# current_amplifier_02.net
KiCad netlist of a schematic drawn in Altium Designer
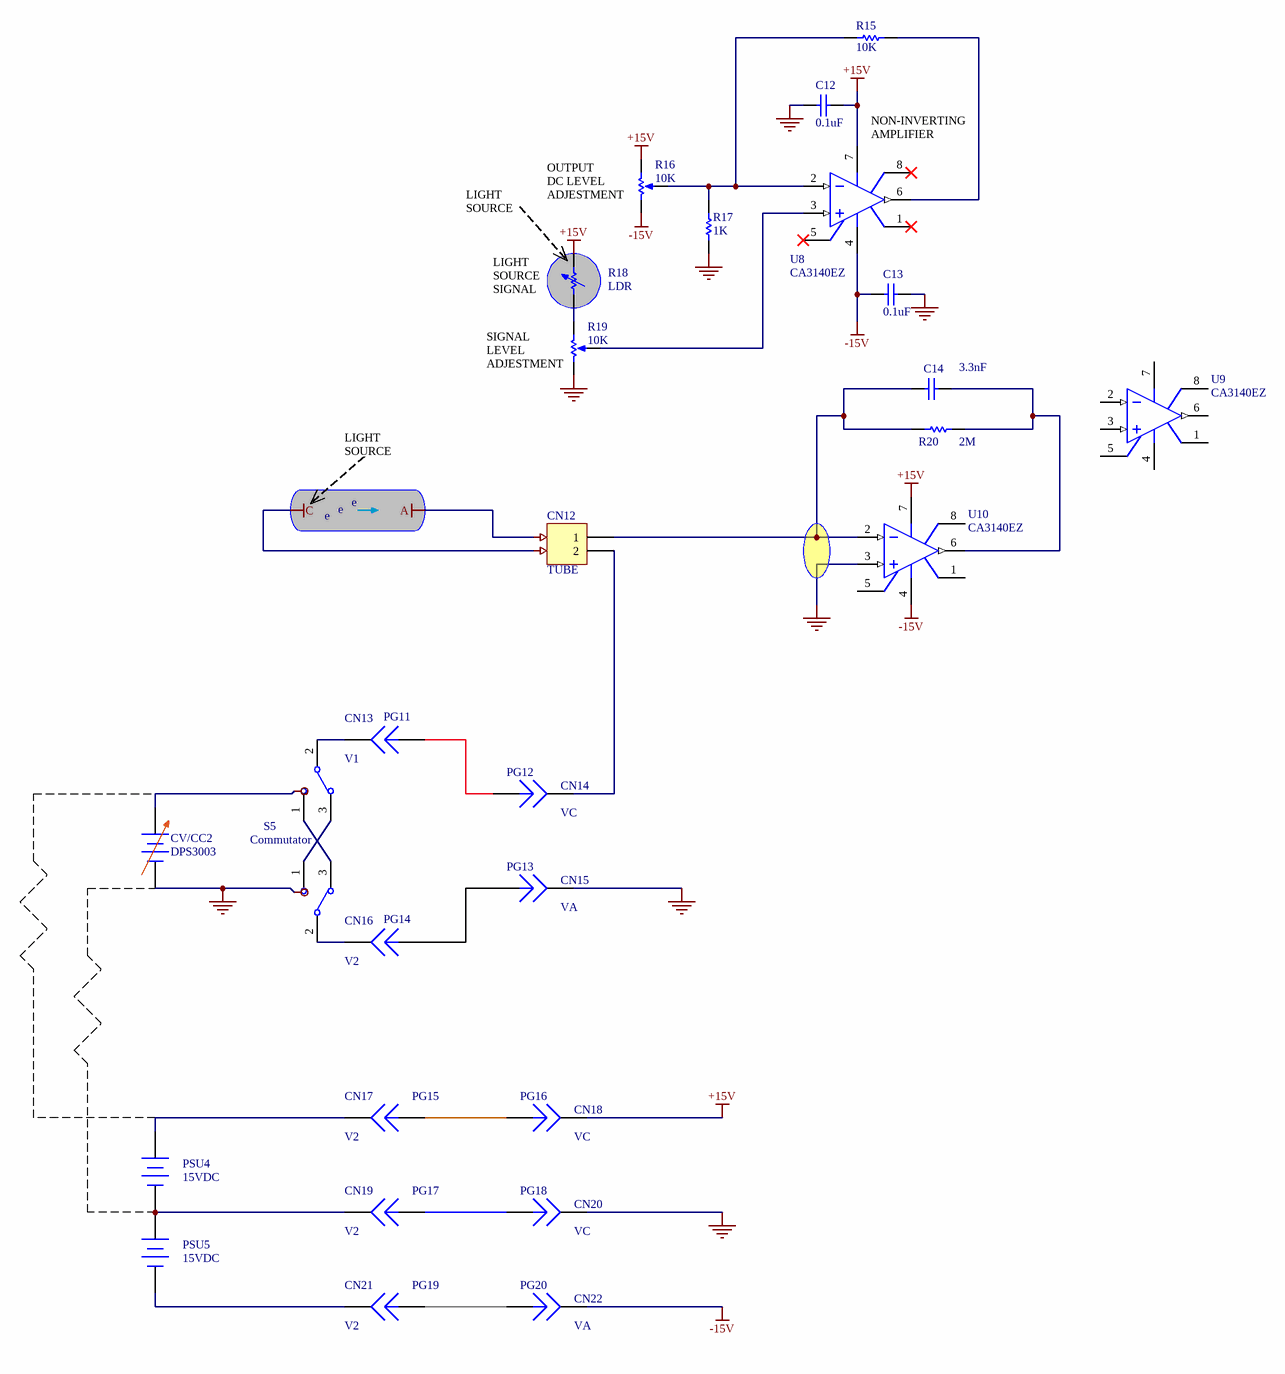
[diagram p0: current amplifier 02.SchDoc]

(export (version "E")
  (design (tool "Eeschema 10.0.6"))
  (components
    (comp (ref "C12")
      (value "0.1uF")
      (footprint "RAD-0.3")
      (description "Capacitor")
      (fields (field (name "PUBLISHER") "Altium Limited"))
      (libsource (lib "Miscellaneous Devices") (part "Cap"))
    )
    (comp (ref "C13")
      (value "0.1uF")
      (footprint "RAD-0.3")
      (description "Capacitor")
      (fields (field (name "PUBLISHER") "Altium Limited"))
      (libsource (lib "Miscellaneous Devices") (part "Cap"))
    )
    (comp (ref "C14")
      (value "3.3nF")
      (footprint "RAD-0.3")
      (description "Capacitor")
      (fields (field (name "PUBLISHER") "Altium Limited"))
      (libsource (lib "Miscellaneous Devices") (part "Cap"))
    )
    (comp (ref "CN12")
      (value "TUBE")
      (footprint "HDR1X2")
      (description "Header, 2-Pin")
      (fields (field (name "PUBLISHER") "Altium Limited"))
      (libsource (lib "Miscellaneous Connectors") (part "Header 2"))
    )
    (comp (ref "CN13")
      (value "V1")
      (footprint "PIN1")
      (description "Socket")
      (fields (field (name "PUBLISHER") "Altium Limited"))
      (libsource (lib "Miscellaneous Connectors") (part "Socket"))
    )
    (comp (ref "CN14")
      (value "VC")
      (footprint "PIN1")
      (description "Socket")
      (fields (field (name "PUBLISHER") "Altium Limited"))
      (libsource (lib "Miscellaneous Connectors") (part "Socket"))
    )
    (comp (ref "CN15")
      (value "VA")
      (footprint "PIN1")
      (description "Socket")
      (fields (field (name "PUBLISHER") "Altium Limited"))
      (libsource (lib "Miscellaneous Connectors") (part "Socket"))
    )
    (comp (ref "CN16")
      (value "V2")
      (footprint "PIN1")
      (description "Socket")
      (fields (field (name "PUBLISHER") "Altium Limited"))
      (libsource (lib "Miscellaneous Connectors") (part "Socket"))
    )
    (comp (ref "CN17")
      (value "V2")
      (footprint "PIN1")
      (description "Socket")
      (fields (field (name "PUBLISHER") "Altium Limited"))
      (libsource (lib "Miscellaneous Connectors") (part "Socket"))
    )
    (comp (ref "CN18")
      (value "VC")
      (footprint "PIN1")
      (description "Socket")
      (fields (field (name "PUBLISHER") "Altium Limited"))
      (libsource (lib "Miscellaneous Connectors") (part "Socket"))
    )
    (comp (ref "CN19")
      (value "V2")
      (footprint "PIN1")
      (description "Socket")
      (fields (field (name "PUBLISHER") "Altium Limited"))
      (libsource (lib "Miscellaneous Connectors") (part "Socket"))
    )
    (comp (ref "CN20")
      (value "VC")
      (footprint "PIN1")
      (description "Socket")
      (fields (field (name "PUBLISHER") "Altium Limited"))
      (libsource (lib "Miscellaneous Connectors") (part "Socket"))
    )
    (comp (ref "CN21")
      (value "V2")
      (footprint "PIN1")
      (description "Socket")
      (fields (field (name "PUBLISHER") "Altium Limited"))
      (libsource (lib "Miscellaneous Connectors") (part "Socket"))
    )
    (comp (ref "CN22")
      (value "VA")
      (footprint "PIN1")
      (description "Socket")
      (fields (field (name "PUBLISHER") "Altium Limited"))
      (libsource (lib "Miscellaneous Connectors") (part "Socket"))
    )
    (comp (ref "CV/CC2")
      (value "DPS3003")
      (footprint "BAT-2")
      (description "Multicell Battery")
      (fields (field (name "PUBLISHER") "Altium Limited"))
      (libsource (lib "Miscellaneous Devices") (part "Battery"))
    )
    (comp (ref "PG11")
      (value "Plug")
      (footprint "PIN1")
      (fields (field (name "PUBLISHER") "Altium Limited"))
      (libsource (lib "Miscellaneous Connectors") (part "Plug"))
    )
    (comp (ref "PG12")
      (value "Plug")
      (footprint "PIN1")
      (fields (field (name "PUBLISHER") "Altium Limited"))
      (libsource (lib "Miscellaneous Connectors") (part "Plug"))
    )
    (comp (ref "PG13")
      (value "Plug")
      (footprint "PIN1")
      (fields (field (name "PUBLISHER") "Altium Limited"))
      (libsource (lib "Miscellaneous Connectors") (part "Plug"))
    )
    (comp (ref "PG14")
      (value "Plug")
      (footprint "PIN1")
      (fields (field (name "PUBLISHER") "Altium Limited"))
      (libsource (lib "Miscellaneous Connectors") (part "Plug"))
    )
    (comp (ref "PG15")
      (value "Plug")
      (footprint "PIN1")
      (fields (field (name "PUBLISHER") "Altium Limited"))
      (libsource (lib "Miscellaneous Connectors") (part "Plug"))
    )
    (comp (ref "PG16")
      (value "Plug")
      (footprint "PIN1")
      (fields (field (name "PUBLISHER") "Altium Limited"))
      (libsource (lib "Miscellaneous Connectors") (part "Plug"))
    )
    (comp (ref "PG17")
      (value "Plug")
      (footprint "PIN1")
      (fields (field (name "PUBLISHER") "Altium Limited"))
      (libsource (lib "Miscellaneous Connectors") (part "Plug"))
    )
    (comp (ref "PG18")
      (value "Plug")
      (footprint "PIN1")
      (fields (field (name "PUBLISHER") "Altium Limited"))
      (libsource (lib "Miscellaneous Connectors") (part "Plug"))
    )
    (comp (ref "PG19")
      (value "Plug")
      (footprint "PIN1")
      (fields (field (name "PUBLISHER") "Altium Limited"))
      (libsource (lib "Miscellaneous Connectors") (part "Plug"))
    )
    (comp (ref "PG20")
      (value "Plug")
      (footprint "PIN1")
      (fields (field (name "PUBLISHER") "Altium Limited"))
      (libsource (lib "Miscellaneous Connectors") (part "Plug"))
    )
    (comp (ref "PSU4")
      (value "15VDC")
      (footprint "BAT-2")
      (description "Multicell Battery")
      (fields (field (name "PUBLISHER") "Altium Limited"))
      (libsource (lib "Miscellaneous Devices") (part "Battery"))
    )
    (comp (ref "PSU5")
      (value "15VDC")
      (footprint "BAT-2")
      (description "Multicell Battery")
      (fields (field (name "PUBLISHER") "Altium Limited"))
      (libsource (lib "Miscellaneous Devices") (part "Battery"))
    )
    (comp (ref "R15")
      (value "10K")
      (footprint "AXIAL-0.3")
      (description "Resistor")
      (fields (field (name "PUBLISHER") "Altium Limited"))
      (libsource (lib "Miscellaneous Devices") (part "Res1"))
    )
    (comp (ref "R16")
      (value "10K")
      (footprint "VR5")
      (description "Potentiometer")
      (fields (field (name "PUBLISHER") "Altium Limited"))
      (libsource (lib "Miscellaneous Devices") (part "RPot"))
    )
    (comp (ref "R17")
      (value "1K")
      (footprint "AXIAL-0.3")
      (description "Resistor")
      (fields (field (name "PUBLISHER") "Altium Limited"))
      (libsource (lib "Miscellaneous Devices") (part "Res1"))
    )
    (comp (ref "R18")
      (value "LDR")
      (footprint "AXIAL-0.7")
      (description "Variable Resistor")
      (fields (field (name "PUBLISHER") "Altium Limited"))
      (libsource (lib "Miscellaneous Devices") (part "Res Adj1"))
    )
    (comp (ref "R19")
      (value "10K")
      (footprint "VR5")
      (description "Potentiometer")
      (fields (field (name "PUBLISHER") "Altium Limited"))
      (libsource (lib "Miscellaneous Devices") (part "RPot"))
    )
    (comp (ref "R20")
      (value "2M")
      (footprint "AXIAL-0.3")
      (description "Resistor")
      (fields (field (name "PUBLISHER") "Altium Limited"))
      (libsource (lib "Miscellaneous Devices") (part "Res1"))
    )
    (comp (ref "S5")
      (value "Commutator")
      (footprint "TL36WW15050")
      (description "SPDT Subminiature Toggle Switch, Right Angle Mounting, Vertical Actuation")
      (fields (field (name "PUBLISHER") "Altium Limited"))
      (libsource (lib "Miscellaneous Devices") (part "SW-SPDT"))
    )
    (comp (ref "S6")
      (value "SW-SPDT")
      (footprint "TL36WW15050")
      (description "SPDT Subminiature Toggle Switch, Right Angle Mounting, Vertical Actuation")
      (fields (field (name "PUBLISHER") "Altium Limited"))
      (libsource (lib "Miscellaneous Devices") (part "SW-SPDT"))
    )
    (comp (ref "U8")
      (value "CA3140EZ")
      (footprint "H-08A")
      (description "FET Operational Amplifier")
      (fields (field (name "PUBLISHER") "Altium Limited"))
      (libsource (lib "Miscellaneous Devices") (part "Op Amp"))
    )
    (comp (ref "U9")
      (value "CA3140EZ")
      (footprint "H-08A")
      (description "FET Operational Amplifier")
      (fields (field (name "PUBLISHER") "Altium Limited"))
      (libsource (lib "Miscellaneous Devices") (part "Op Amp"))
    )
    (comp (ref "U10")
      (value "CA3140EZ")
      (footprint "H-08A")
      (description "FET Operational Amplifier")
      (fields (field (name "PUBLISHER") "Altium Limited"))
      (libsource (lib "Miscellaneous Devices") (part "Op Amp"))
    )
  )
  (nets
    (net (code "1") (name "+15V") (class "Default")
      (node (ref "C12") (pin "2") (pinfunction "2_2") (pintype "passive"))
      (node (ref "CN18") (pin "1") (pinfunction "1_1") (pintype "passive"))
      (node (ref "R16") (pin "1") (pinfunction "TOP_1") (pintype "passive"))
      (node (ref "R18") (pin "2") (pinfunction "2_2") (pintype "passive"))
      (node (ref "U10") (pin "7") (pinfunction "V+_7") (pintype "power_in"))
      (node (ref "U8") (pin "7") (pinfunction "V+_7") (pintype "power_in"))
    )
    (net (code "2") (name "-15V") (class "Default")
      (node (ref "C13") (pin "1") (pinfunction "1_1") (pintype "passive"))
      (node (ref "CN22") (pin "1") (pinfunction "1_1") (pintype "passive"))
      (node (ref "R16") (pin "2") (pinfunction "BOT_2") (pintype "passive"))
      (node (ref "U10") (pin "4") (pinfunction "V-_4") (pintype "power_in"))
      (node (ref "U8") (pin "4") (pinfunction "V-_4") (pintype "power_in"))
    )
    (net (code "3") (name "A") (class "Default")
      (node (ref "C12") (pin "1") (pinfunction "1_1") (pintype "passive"))
      (node (ref "C13") (pin "2") (pinfunction "2_2") (pintype "passive"))
      (node (ref "CN15") (pin "1") (pinfunction "1_1") (pintype "passive"))
      (node (ref "CN20") (pin "1") (pinfunction "1_1") (pintype "passive"))
      (node (ref "CV/CC2") (pin "1") (pinfunction "+_1") (pintype "passive"))
      (node (ref "CV/CC2") (pin "2") (pinfunction "-_2") (pintype "passive"))
      (node (ref "R17") (pin "1") (pinfunction "1_1") (pintype "passive"))
      (node (ref "R19") (pin "2") (pinfunction "BOT_2") (pintype "passive"))
      (node (ref "U10") (pin "3") (pinfunction "IN+_3") (pintype "input"))
    )
    (net (code "4") (name "Net-(CN12-Pad2)") (class "Default")
      (node (ref "CN12") (pin "2") (pinfunction "2_2") (pintype "passive"))
      (node (ref "CN14") (pin "1") (pinfunction "1_1") (pintype "passive"))
    )
    (net (code "5") (name "Net-(CN13-Pad1)") (class "Default")
      (node (ref "CN13") (pin "1") (pinfunction "1_1") (pintype "passive"))
      (node (ref "S5") (pin "2") (pinfunction "2_2") (pintype "passive"))
    )
    (net (code "6") (name "Net-(CN16-Pad1)") (class "Default")
      (node (ref "CN16") (pin "1") (pinfunction "1_1") (pintype "passive"))
      (node (ref "S6") (pin "2") (pinfunction "2_2") (pintype "passive"))
    )
    (net (code "7") (name "Net-(PG11-Pad1)") (class "Default")
      (node (ref "PG11") (pin "1") (pinfunction "1_1") (pintype "passive"))
      (node (ref "PG12") (pin "1") (pinfunction "1_1") (pintype "passive"))
    )
    (net (code "8") (name "Net-(PG13-Pad1)") (class "Default")
      (node (ref "PG13") (pin "1") (pinfunction "1_1") (pintype "passive"))
      (node (ref "PG14") (pin "1") (pinfunction "1_1") (pintype "passive"))
    )
    (net (code "9") (name "Net-(PG15-Pad1)") (class "Default")
      (node (ref "PG15") (pin "1") (pinfunction "1_1") (pintype "passive"))
      (node (ref "PG16") (pin "1") (pinfunction "1_1") (pintype "passive"))
    )
    (net (code "10") (name "Net-(PG17-Pad1)") (class "Default")
      (node (ref "PG17") (pin "1") (pinfunction "1_1") (pintype "passive"))
      (node (ref "PG18") (pin "1") (pinfunction "1_1") (pintype "passive"))
    )
    (net (code "11") (name "Net-(PG19-Pad1)") (class "Default")
      (node (ref "PG19") (pin "1") (pinfunction "1_1") (pintype "passive"))
      (node (ref "PG20") (pin "1") (pinfunction "1_1") (pintype "passive"))
    )
    (net (code "12") (name "Net-(PSU4-+)") (class "Default")
      (node (ref "CN17") (pin "1") (pinfunction "1_1") (pintype "passive"))
      (node (ref "PSU4") (pin "1") (pinfunction "+_1") (pintype "passive"))
    )
    (net (code "13") (name "Net-(PSU4--)") (class "Default")
      (node (ref "CN19") (pin "1") (pinfunction "1_1") (pintype "passive"))
      (node (ref "PSU4") (pin "2") (pinfunction "-_2") (pintype "passive"))
      (node (ref "PSU5") (pin "1") (pinfunction "+_1") (pintype "passive"))
    )
    (net (code "14") (name "Net-(PSU5--)") (class "Default")
      (node (ref "CN21") (pin "1") (pinfunction "1_1") (pintype "passive"))
      (node (ref "PSU5") (pin "2") (pinfunction "-_2") (pintype "passive"))
    )
    (net (code "15") (name "Net-(R16-TAP)") (class "Default")
      (node (ref "R15") (pin "1") (pinfunction "1_1") (pintype "passive"))
      (node (ref "R16") (pin "3") (pinfunction "TAP_3") (pintype "passive"))
      (node (ref "R17") (pin "2") (pinfunction "2_2") (pintype "passive"))
      (node (ref "U8") (pin "2") (pinfunction "IN-_2") (pintype "input"))
    )
    (net (code "16") (name "Net-(R19-TAP)") (class "Default")
      (node (ref "R19") (pin "3") (pinfunction "TAP_3") (pintype "passive"))
      (node (ref "U8") (pin "3") (pinfunction "IN+_3") (pintype "input"))
    )
    (net (code "17") (name "Net-(R19-TOP)") (class "Default")
      (node (ref "R18") (pin "1") (pinfunction "1_1") (pintype "passive"))
      (node (ref "R19") (pin "1") (pinfunction "TOP_1") (pintype "passive"))
    )
    (net (code "18") (name "Net-(S5-Pad1)") (class "Default")
      (node (ref "S5") (pin "1") (pinfunction "1_1") (pintype "passive"))
      (node (ref "S6") (pin "3") (pinfunction "3_3") (pintype "passive"))
    )
    (net (code "19") (name "Net-(S5-Pad3)") (class "Default")
      (node (ref "S5") (pin "3") (pinfunction "3_3") (pintype "passive"))
      (node (ref "S6") (pin "1") (pinfunction "1_1") (pintype "passive"))
    )
    (net (code "20") (name "Net-(U8-OUT)") (class "Default")
      (node (ref "R15") (pin "2") (pinfunction "2_2") (pintype "passive"))
      (node (ref "U8") (pin "6") (pinfunction "OUT_6") (pintype "output"))
    )
    (net (code "21") (name "Net-(U10-IN-)") (class "Default")
      (node (ref "C14") (pin "1") (pinfunction "1_1") (pintype "passive"))
      (node (ref "CN12") (pin "1") (pinfunction "1_1") (pintype "passive"))
      (node (ref "R20") (pin "1") (pinfunction "1_1") (pintype "passive"))
      (node (ref "U10") (pin "2") (pinfunction "IN-_2") (pintype "input"))
    )
    (net (code "22") (name "Net-(U10-OUT)") (class "Default")
      (node (ref "C14") (pin "2") (pinfunction "2_2") (pintype "passive"))
      (node (ref "R20") (pin "2") (pinfunction "2_2") (pintype "passive"))
      (node (ref "U10") (pin "6") (pinfunction "OUT_6") (pintype "output"))
    )
    (net (code "23") (name "unconnected-(U8-OS_NUL-Pad1)") (class "Default")
      (node (ref "U8") (pin "1") (pinfunction "OS_NUL_1") (pintype "passive+no_connect"))
    )
    (net (code "24") (name "unconnected-(U8-OS_NUL-Pad5)") (class "Default")
      (node (ref "U8") (pin "5") (pinfunction "OS_NUL_5") (pintype "passive+no_connect"))
    )
    (net (code "25") (name "unconnected-(U8-TAB-Pad8)") (class "Default")
      (node (ref "U8") (pin "8") (pinfunction "TAB_8") (pintype "passive+no_connect"))
    )
    (net (code "26") (name "unconnected-(U9-IN+-Pad3)") (class "Default")
      (node (ref "U9") (pin "3") (pinfunction "IN+_3") (pintype "input"))
    )
    (net (code "27") (name "unconnected-(U9-IN--Pad2)") (class "Default")
      (node (ref "U9") (pin "2") (pinfunction "IN-_2") (pintype "input"))
    )
    (net (code "28") (name "unconnected-(U9-OS_NUL-Pad1)") (class "Default")
      (node (ref "U9") (pin "1") (pinfunction "OS_NUL_1") (pintype "passive"))
    )
    (net (code "29") (name "unconnected-(U9-OS_NUL-Pad5)") (class "Default")
      (node (ref "U9") (pin "5") (pinfunction "OS_NUL_5") (pintype "passive"))
    )
    (net (code "30") (name "unconnected-(U9-OUT-Pad6)") (class "Default")
      (node (ref "U9") (pin "6") (pinfunction "OUT_6") (pintype "output"))
    )
    (net (code "31") (name "unconnected-(U9-TAB-Pad8)") (class "Default")
      (node (ref "U9") (pin "8") (pinfunction "TAB_8") (pintype "passive"))
    )
    (net (code "32") (name "unconnected-(U9-V+-Pad7)") (class "Default")
      (node (ref "U9") (pin "7") (pinfunction "V+_7") (pintype "power_in"))
    )
    (net (code "33") (name "unconnected-(U9-V--Pad4)") (class "Default")
      (node (ref "U9") (pin "4") (pinfunction "V-_4") (pintype "power_in"))
    )
    (net (code "34") (name "unconnected-(U10-OS_NUL-Pad1)") (class "Default")
      (node (ref "U10") (pin "1") (pinfunction "OS_NUL_1") (pintype "passive"))
    )
    (net (code "35") (name "unconnected-(U10-OS_NUL-Pad5)") (class "Default")
      (node (ref "U10") (pin "5") (pinfunction "OS_NUL_5") (pintype "passive"))
    )
    (net (code "36") (name "unconnected-(U10-TAB-Pad8)") (class "Default")
      (node (ref "U10") (pin "8") (pinfunction "TAB_8") (pintype "passive"))
    )
  )
)
